# wyrbondr.net
KiCad netlist of a schematic drawn in EAGLE
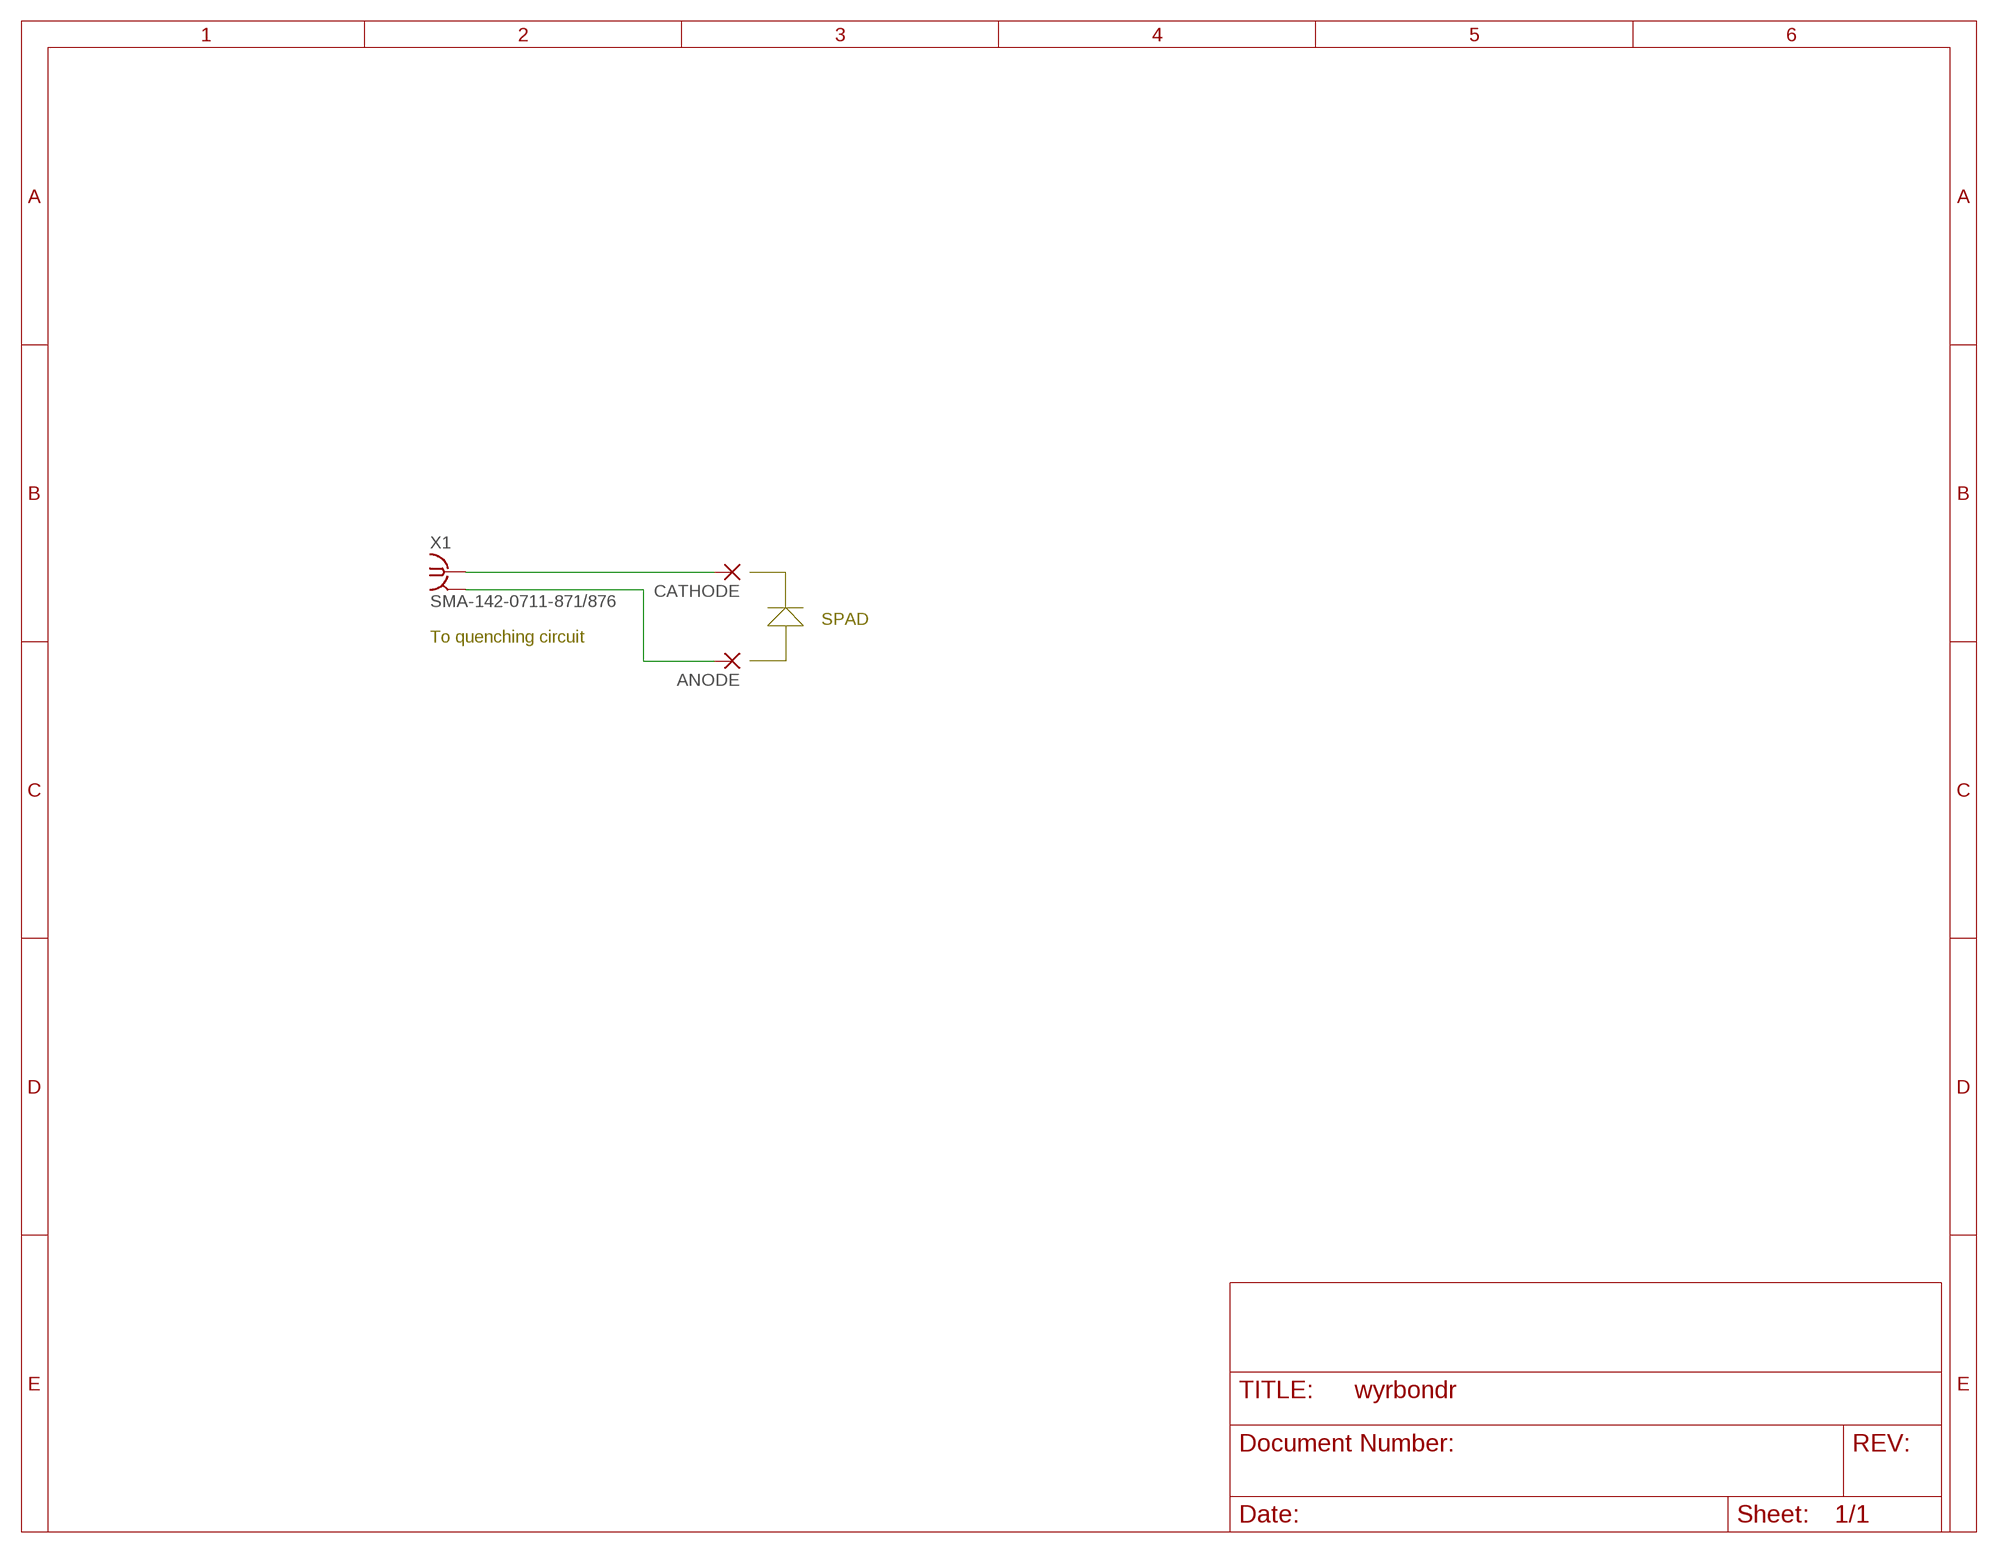
[diagram p0: schematic, sheet 1]

(export (version "E")
  (design (tool "Eeschema 10.0.6"))
  (components
    (comp (ref "ANODE")
      (value "SMD2")
      (footprint "eagle-import:SMD1,27-2,54")
      (libsource (lib "eagle-import") (part "SMD2"))
    )
    (comp (ref "CATHODE")
      (value "SMD2")
      (footprint "eagle-import:SMD1,27-2,54")
      (libsource (lib "eagle-import") (part "SMD2"))
    )
    (comp (ref "X1")
      (value "SMA-142-0711-871/876")
      (footprint "eagle-import:J502-ND-142-0711-871_876")
      (fields (field (name "MF") "JOHNSON COMPONENTS") (field (name "MPN") "142-0711-871"))
      (libsource (lib "eagle-import") (part "SMA-142-0711-871/876"))
    )
  )
  (nets
    (net (code "1") (name "Net-(ANODE-P)") (class "Default")
      (node (ref "ANODE") (pin "1") (pinfunction "P_1") (pintype "passive"))
      (node (ref "X1") (pin "G@1") (pinfunction "GND_G@1") (pintype "power_in"))
    )
    (net (code "2") (name "Net-(CATHODE-P)") (class "Default")
      (node (ref "CATHODE") (pin "1") (pinfunction "P_1") (pintype "passive"))
      (node (ref "X1") (pin "1") (pinfunction "1_1") (pintype "passive"))
    )
  )
)
